# PM12_P3V8.net
KiCad netlist of a schematic drawn in Altium Designer
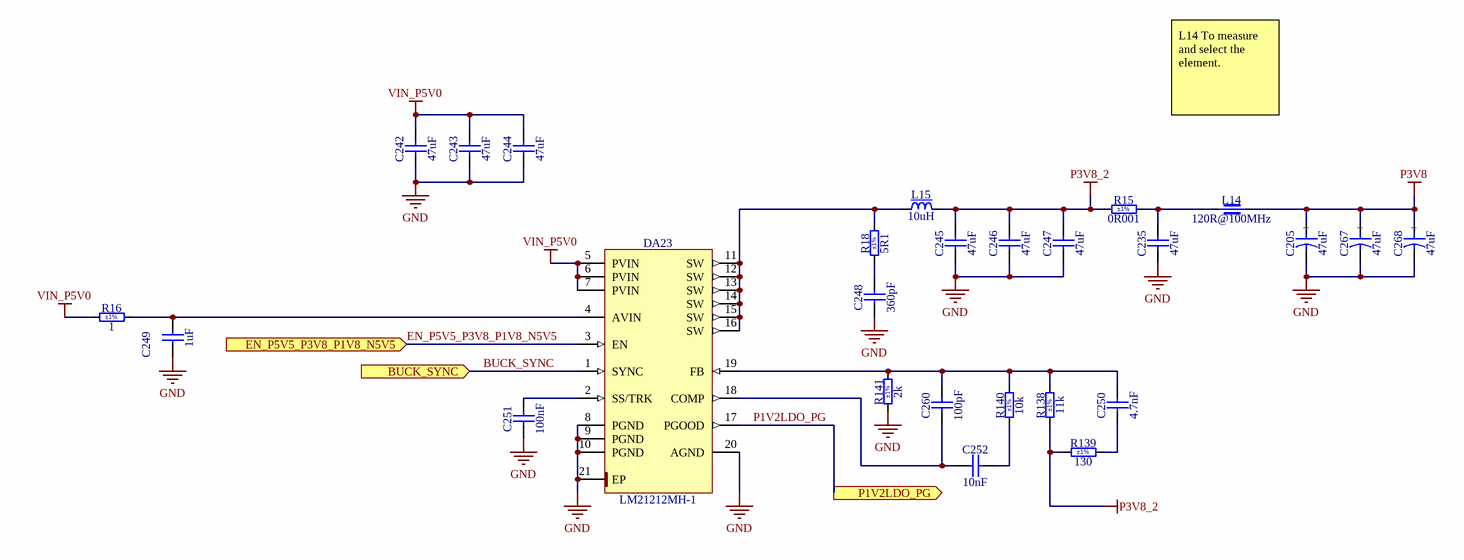
[diagram p0: PM12_P3V8.SchDoc]

(export (version "E")
  (design (tool "Eeschema 10.0.6"))
  (components
    (comp (ref "C205")
      (value "47uF")
      (footprint "CAPAE530X610N")
      (description "Polarised capacitor")
      (fields
        (field (name "PART NUMBER") "CAE530-610_47UF_16V_20%")
        (field (name "VOLTAGE") "16V")
        (field (name "AUTHOR") "CERN DEM HF")
      )
      (libsource (lib "Capacitors") (part "Capacitor - polarized"))
    )
    (comp (ref "C235")
      (value "47uF")
      (footprint "CAPC3225X270N")
      (description "Non-polarised capacitor")
      (fields
        (field (name "PART NUMBER") "CC1210_47UF_16V_20%_X5R")
        (field (name "VOLTAGE") "16V")
        (field (name "AUTHOR") "CERN DEM MR")
      )
      (libsource (lib "Capacitors") (part "Capacitor - non polarized"))
    )
    (comp (ref "C242")
      (value "47uF")
      (footprint "CAPC3225X270N")
      (description "Non-polarised capacitor")
      (fields
        (field (name "PART NUMBER") "CC1210_47UF_16V_20%_X5R")
        (field (name "VOLTAGE") "16V")
        (field (name "AUTHOR") "CERN DEM MR")
      )
      (libsource (lib "Capacitors") (part "Capacitor - non polarized"))
    )
    (comp (ref "C243")
      (value "47uF")
      (footprint "CAPC3225X270N")
      (description "Non-polarised capacitor")
      (fields
        (field (name "PART NUMBER") "CC1210_47UF_16V_20%_X5R")
        (field (name "VOLTAGE") "16V")
        (field (name "AUTHOR") "CERN DEM MR")
      )
      (libsource (lib "Capacitors") (part "Capacitor - non polarized"))
    )
    (comp (ref "C244")
      (value "47uF")
      (footprint "CAPC3225X270N")
      (description "Non-polarised capacitor")
      (fields
        (field (name "PART NUMBER") "CC1210_47UF_16V_20%_X5R")
        (field (name "VOLTAGE") "16V")
        (field (name "AUTHOR") "CERN DEM MR")
      )
      (libsource (lib "Capacitors") (part "Capacitor - non polarized"))
    )
    (comp (ref "C245")
      (value "47uF")
      (footprint "CAPC3225X270N")
      (description "Non-polarised capacitor")
      (fields
        (field (name "PART NUMBER") "CC1210_47UF_16V_20%_X5R")
        (field (name "VOLTAGE") "16V")
        (field (name "AUTHOR") "CERN DEM MR")
      )
      (libsource (lib "Capacitors") (part "Capacitor - non polarized"))
    )
    (comp (ref "C246")
      (value "47uF")
      (footprint "CAPC3225X270N")
      (description "Non-polarised capacitor")
      (fields
        (field (name "PART NUMBER") "CC1210_47UF_16V_20%_X5R")
        (field (name "VOLTAGE") "16V")
        (field (name "AUTHOR") "CERN DEM MR")
      )
      (libsource (lib "Capacitors") (part "Capacitor - non polarized"))
    )
    (comp (ref "C247")
      (value "47uF")
      (footprint "CAPC3225X270N")
      (description "Non-polarised capacitor")
      (fields
        (field (name "PART NUMBER") "CC1210_47UF_16V_20%_X5R")
        (field (name "VOLTAGE") "16V")
        (field (name "AUTHOR") "CERN DEM MR")
      )
      (libsource (lib "Capacitors") (part "Capacitor - non polarized"))
    )
    (comp (ref "C248")
      (value "360pF")
      (footprint "CAPC2013X145N")
      (description "Non-polarised capacitor")
      (fields
        (field (name "PART NUMBER") "CC0805_360PF_50V_5%_C0G")
        (field (name "VOLTAGE") "50V")
        (field (name "AUTHOR") "CERN DEM HF")
      )
      (libsource (lib "Capacitors") (part "Capacitor - non polarized"))
    )
    (comp (ref "C249")
      (value "1uF")
      (footprint "CAPC2012X140N")
      (description "Non-polarised capacitor")
      (fields
        (field (name "PART NUMBER") "CC0805_1UF_25V_10%_X7R")
        (field (name "VOLTAGE") "25V")
        (field (name "AUTHOR") "CERN DEM JLC")
      )
      (libsource (lib "Capacitors") (part "Capacitor - non polarized"))
    )
    (comp (ref "C250")
      (value "4.7nF")
      (footprint "CAPC2012X135N")
      (description "Non-polarised capacitor")
      (fields
        (field (name "PART NUMBER") "CC0805_4.7NF_50V_10%_X7R")
        (field (name "VOLTAGE") "50V")
        (field (name "AUTHOR") "CERN DEM JLC")
      )
      (libsource (lib "Capacitors") (part "Capacitor - non polarized"))
    )
    (comp (ref "C251")
      (value "100nF")
      (footprint "CAPC2012X135N")
      (description "Non-polarised capacitor")
      (fields
        (field (name "PART NUMBER") "CC0805_100NF_50V_10%_X7R")
        (field (name "VOLTAGE") "50V")
        (field (name "AUTHOR") "CERN DEM JLC")
      )
      (libsource (lib "Capacitors") (part "Capacitor - non polarized"))
    )
    (comp (ref "C252")
      (value "10nF")
      (footprint "CAPC2012X135N")
      (description "Non-polarised capacitor")
      (fields
        (field (name "PART NUMBER") "CC0805_10NF_50V_10%_X7R")
        (field (name "VOLTAGE") "50V")
        (field (name "AUTHOR") "CERN DEM JLC")
      )
      (libsource (lib "Capacitors") (part "Capacitor - non polarized"))
    )
    (comp (ref "C260")
      (value "100pF")
      (footprint "CAPC2012X135N")
      (description "Non-polarised capacitor")
      (fields
        (field (name "PART NUMBER") "CC0805_100PF_50V_5%_NP0")
        (field (name "VOLTAGE") "50V")
        (field (name "AUTHOR") "CERN DEM JLC")
      )
      (libsource (lib "Capacitors") (part "Capacitor - non polarized"))
    )
    (comp (ref "C267")
      (value "47uF")
      (footprint "CAPAE530X610N")
      (description "Polarised capacitor")
      (fields
        (field (name "PART NUMBER") "CAE530-610_47UF_16V_20%")
        (field (name "VOLTAGE") "16V")
        (field (name "AUTHOR") "CERN DEM HF")
      )
      (libsource (lib "Capacitors") (part "Capacitor - polarized"))
    )
    (comp (ref "C268")
      (value "47uF")
      (footprint "CAPAE530X610N")
      (description "Polarised capacitor")
      (fields
        (field (name "PART NUMBER") "CAE530-610_47UF_16V_20%")
        (field (name "VOLTAGE") "16V")
        (field (name "AUTHOR") "CERN DEM HF")
      )
      (libsource (lib "Capacitors") (part "Capacitor - polarized"))
    )
    (comp (ref "DA23")
      (value "LM21212MH-1")
      (footprint "TEXAS_PWP0020AA")
      (description "2.95-V To 5.5-V, 12-A, Voltage-Mode Synchronous Buck Regulator with Frequency Synchronization")
      (fields (field (name "MANUFACTURER") "TEXAS INSTRUMENTS") (field (name "AUTHOR") "CERN DEM HF"))
      (libsource (lib "ICs And Semiconductors") (part "LM21212"))
    )
    (comp (ref "L14")
      (value "120R@100MHz")
      (footprint "IND_MURATA_BLM31KN")
      (fields
        (field (name "PART NUMBER") "IND1206_MURATA_BLM31KN121SN1")
        (field (name "POWER") "6A")
        (field (name "TOLERANCE") "±25%")
        (field (name "AUTHOR") "CERN DEM HF")
      )
      (libsource (lib "Inductors & Transformers") (part "Ferrite Bead"))
    )
    (comp (ref "L15")
      (value "10uH")
      (footprint "IND_VISHAY_IHPL4040DZ-01")
      (description "Inductor With Core")
      (fields
        (field (name "PART NUMBER") "IND4040_10UH_20%_VISHAY_IHLP-4040DZ-01")
        (field (name "POWER") "6.8A")
        (field (name "AUTHOR") "CERN DEM HF")
      )
      (libsource (lib "Inductors & Transformers") (part "Inductor With Magnetic core"))
    )
    (comp (ref "R15")
      (value "0R001")
      (footprint "RESC_BOURNS_CRE2512_0R001-0R004")
      (description "Resistor - 1%")
      (fields
        (field (name "TOLERANCE") "±1%")
        (field (name "PART NUMBER") "R2512_0R001_1%_3W_50PPM_BOURNS_CRE2512")
        (field (name "POWER") "3W")
        (field (name "AUTHOR") "CERN DEM BC")
      )
      (libsource (lib "Resistors") (part "Resistor - 1%"))
    )
    (comp (ref "R16")
      (value "1")
      (footprint "RESC2012X60N")
      (description "Resistor - 1%")
      (fields
        (field (name "TOLERANCE") "±1%")
        (field (name "PART NUMBER") "R0805_1R_1%_0.125W_100PPM")
        (field (name "POWER") "0.125W")
        (field (name "AUTHOR") "CERN DEM HF")
      )
      (libsource (lib "Resistors") (part "Resistor - 1%"))
    )
    (comp (ref "R18")
      (value "5R1")
      (footprint "RESC2012X60N")
      (description "Resistor - 1%")
      (fields
        (field (name "TOLERANCE") "±1%")
        (field (name "PART NUMBER") "R0805_5R1_1%_0.125W_100PPM")
        (field (name "POWER") "0.125W")
        (field (name "AUTHOR") "CERN DEM HF")
      )
      (libsource (lib "Resistors") (part "Resistor - 1%"))
    )
    (comp (ref "R138")
      (value "11k")
      (footprint "RESC2012X60N")
      (description "Resistor - 1%")
      (fields
        (field (name "TOLERANCE") "±1%")
        (field (name "PART NUMBER") "R0805_11K_1%_0.125W_100PPM")
        (field (name "POWER") "0.125W")
        (field (name "AUTHOR") "CERN DEM JLC")
      )
      (libsource (lib "Resistors") (part "Resistor - 1%"))
    )
    (comp (ref "R139")
      (value "130")
      (footprint "RESC2012X60N")
      (description "Resistor - 1%")
      (fields
        (field (name "TOLERANCE") "±1%")
        (field (name "PART NUMBER") "R0805_130R_1%_0.125W_100PPM")
        (field (name "POWER") "0.125W")
        (field (name "AUTHOR") "CERN DEM JLC")
      )
      (libsource (lib "Resistors") (part "Resistor - 1%"))
    )
    (comp (ref "R140")
      (value "10k")
      (footprint "RESC2012X60N")
      (description "Resistor - 1%")
      (fields
        (field (name "TOLERANCE") "±1%")
        (field (name "PART NUMBER") "R0805_10K_1%_0.125W_100PPM")
        (field (name "POWER") "0.125W")
        (field (name "AUTHOR") "CERN DEM JLC")
      )
      (libsource (lib "Resistors") (part "Resistor - 1%"))
    )
    (comp (ref "R141")
      (value "2k")
      (footprint "RESC2012X60N")
      (description "Resistor - 1%")
      (fields
        (field (name "TOLERANCE") "±1%")
        (field (name "PART NUMBER") "R0805_2K_1%_0.125W_100PPM")
        (field (name "POWER") "0.125W")
        (field (name "AUTHOR") "CERN DEM JLC")
      )
      (libsource (lib "Resistors") (part "Resistor - 1%"))
    )
  )
  (nets
    (net (code "1") (name "/BUCK_SYNC") (class "Default")
      (node (ref "DA23") (pin "1") (pinfunction "SYNC_1") (pintype "input"))
    )
    (net (code "2") (name "/EN_P5V5_P3V8_P1V8_N5V5") (class "Default")
      (node (ref "DA23") (pin "3") (pinfunction "EN_3") (pintype "input"))
    )
    (net (code "3") (name "/P1V2LDO_PG") (class "Default")
      (node (ref "DA23") (pin "17") (pinfunction "PGOOD_17") (pintype "output"))
    )
    (net (code "4") (name "GND") (class "Default")
      (node (ref "C205") (pin "2") (pinfunction "2_2") (pintype "passive"))
      (node (ref "C235") (pin "1") (pinfunction "1_1") (pintype "passive"))
      (node (ref "C242") (pin "1") (pinfunction "1_1") (pintype "passive"))
      (node (ref "C243") (pin "1") (pinfunction "1_1") (pintype "passive"))
      (node (ref "C244") (pin "1") (pinfunction "1_1") (pintype "passive"))
      (node (ref "C245") (pin "1") (pinfunction "1_1") (pintype "passive"))
      (node (ref "C246") (pin "1") (pinfunction "1_1") (pintype "passive"))
      (node (ref "C247") (pin "1") (pinfunction "1_1") (pintype "passive"))
      (node (ref "C248") (pin "1") (pinfunction "1_1") (pintype "passive"))
      (node (ref "C249") (pin "1") (pinfunction "1_1") (pintype "passive"))
      (node (ref "C251") (pin "1") (pinfunction "1_1") (pintype "passive"))
      (node (ref "C267") (pin "2") (pinfunction "2_2") (pintype "passive"))
      (node (ref "C268") (pin "2") (pinfunction "2_2") (pintype "passive"))
      (node (ref "DA23") (pin "10") (pinfunction "PGND_10") (pintype "power_in"))
      (node (ref "DA23") (pin "20") (pinfunction "AGND_20") (pintype "power_in"))
      (node (ref "DA23") (pin "21") (pinfunction "EP_21") (pintype "power_in"))
      (node (ref "DA23") (pin "8") (pinfunction "PGND_8") (pintype "power_in"))
      (node (ref "DA23") (pin "9") (pinfunction "PGND_9") (pintype "power_in"))
      (node (ref "R141") (pin "1") (pinfunction "1_1") (pintype "passive"))
    )
    (net (code "5") (name "Net-(C235-Pad2)") (class "Default")
      (node (ref "C235") (pin "2") (pinfunction "2_2") (pintype "passive"))
      (node (ref "L14") (pin "1") (pinfunction "1_1") (pintype "passive"))
      (node (ref "R15") (pin "2") (pinfunction "2_2") (pintype "passive"))
    )
    (net (code "6") (name "Net-(C248-Pad2)") (class "Default")
      (node (ref "C248") (pin "2") (pinfunction "2_2") (pintype "passive"))
      (node (ref "R18") (pin "1") (pinfunction "1_1") (pintype "passive"))
    )
    (net (code "7") (name "Net-(C250-Pad1)") (class "Default")
      (node (ref "C250") (pin "1") (pinfunction "1_1") (pintype "passive"))
      (node (ref "R139") (pin "1") (pinfunction "1_1") (pintype "passive"))
    )
    (net (code "8") (name "Net-(C252-Pad1)") (class "Default")
      (node (ref "C252") (pin "1") (pinfunction "1_1") (pintype "passive"))
      (node (ref "R140") (pin "1") (pinfunction "1_1") (pintype "passive"))
    )
    (net (code "9") (name "Net-(DA23-AVIN)") (class "Default")
      (node (ref "C249") (pin "2") (pinfunction "2_2") (pintype "passive"))
      (node (ref "DA23") (pin "4") (pinfunction "AVIN_4") (pintype "power_in"))
      (node (ref "R16") (pin "2") (pinfunction "2_2") (pintype "passive"))
    )
    (net (code "10") (name "Net-(DA23-COMP)") (class "Default")
      (node (ref "C252") (pin "2") (pinfunction "2_2") (pintype "passive"))
      (node (ref "C260") (pin "1") (pinfunction "1_1") (pintype "passive"))
      (node (ref "DA23") (pin "18") (pinfunction "COMP_18") (pintype "output"))
    )
    (net (code "11") (name "Net-(DA23-FB)") (class "Default")
      (node (ref "C250") (pin "2") (pinfunction "2_2") (pintype "passive"))
      (node (ref "C260") (pin "2") (pinfunction "2_2") (pintype "passive"))
      (node (ref "DA23") (pin "19") (pinfunction "FB_19") (pintype "input"))
      (node (ref "R138") (pin "2") (pinfunction "2_2") (pintype "passive"))
      (node (ref "R140") (pin "2") (pinfunction "2_2") (pintype "passive"))
      (node (ref "R141") (pin "2") (pinfunction "2_2") (pintype "passive"))
    )
    (net (code "12") (name "Net-(DA23-SS{slash}TRK)") (class "Default")
      (node (ref "C251") (pin "2") (pinfunction "2_2") (pintype "passive"))
      (node (ref "DA23") (pin "2") (pinfunction "SS/TRK_2") (pintype "input"))
    )
    (net (code "13") (name "Net-(DA23-SW-Pad11)") (class "Default")
      (node (ref "DA23") (pin "11") (pinfunction "SW_11") (pintype "output"))
      (node (ref "DA23") (pin "12") (pinfunction "SW_12") (pintype "output"))
      (node (ref "DA23") (pin "13") (pinfunction "SW_13") (pintype "output"))
      (node (ref "DA23") (pin "14") (pinfunction "SW_14") (pintype "output"))
      (node (ref "DA23") (pin "15") (pinfunction "SW_15") (pintype "output"))
      (node (ref "DA23") (pin "16") (pinfunction "SW_16") (pintype "output"))
      (node (ref "L15") (pin "1") (pinfunction "1_1") (pintype "passive"))
      (node (ref "R18") (pin "2") (pinfunction "2_2") (pintype "passive"))
    )
    (net (code "14") (name "P3V8") (class "Default")
      (node (ref "C205") (pin "1") (pinfunction "1_1") (pintype "passive"))
      (node (ref "C267") (pin "1") (pinfunction "1_1") (pintype "passive"))
      (node (ref "C268") (pin "1") (pinfunction "1_1") (pintype "passive"))
      (node (ref "L14") (pin "2") (pinfunction "2_2") (pintype "passive"))
    )
    (net (code "15") (name "P3V8_2") (class "Default")
      (node (ref "C245") (pin "2") (pinfunction "2_2") (pintype "passive"))
      (node (ref "C246") (pin "2") (pinfunction "2_2") (pintype "passive"))
      (node (ref "C247") (pin "2") (pinfunction "2_2") (pintype "passive"))
      (node (ref "L15") (pin "2") (pinfunction "2_2") (pintype "passive"))
      (node (ref "R138") (pin "1") (pinfunction "1_1") (pintype "passive"))
      (node (ref "R139") (pin "2") (pinfunction "2_2") (pintype "passive"))
      (node (ref "R15") (pin "1") (pinfunction "1_1") (pintype "passive"))
    )
    (net (code "16") (name "VIN_P5V0") (class "Default")
      (node (ref "C242") (pin "2") (pinfunction "2_2") (pintype "passive"))
      (node (ref "C243") (pin "2") (pinfunction "2_2") (pintype "passive"))
      (node (ref "C244") (pin "2") (pinfunction "2_2") (pintype "passive"))
      (node (ref "DA23") (pin "5") (pinfunction "PVIN_5") (pintype "power_in"))
      (node (ref "DA23") (pin "6") (pinfunction "PVIN_6") (pintype "power_in"))
      (node (ref "DA23") (pin "7") (pinfunction "PVIN_7") (pintype "power_in"))
      (node (ref "R16") (pin "1") (pinfunction "1_1") (pintype "passive"))
    )
  )
)
